# 7_VGA.net
KiCad netlist of a schematic drawn in Altium Designer
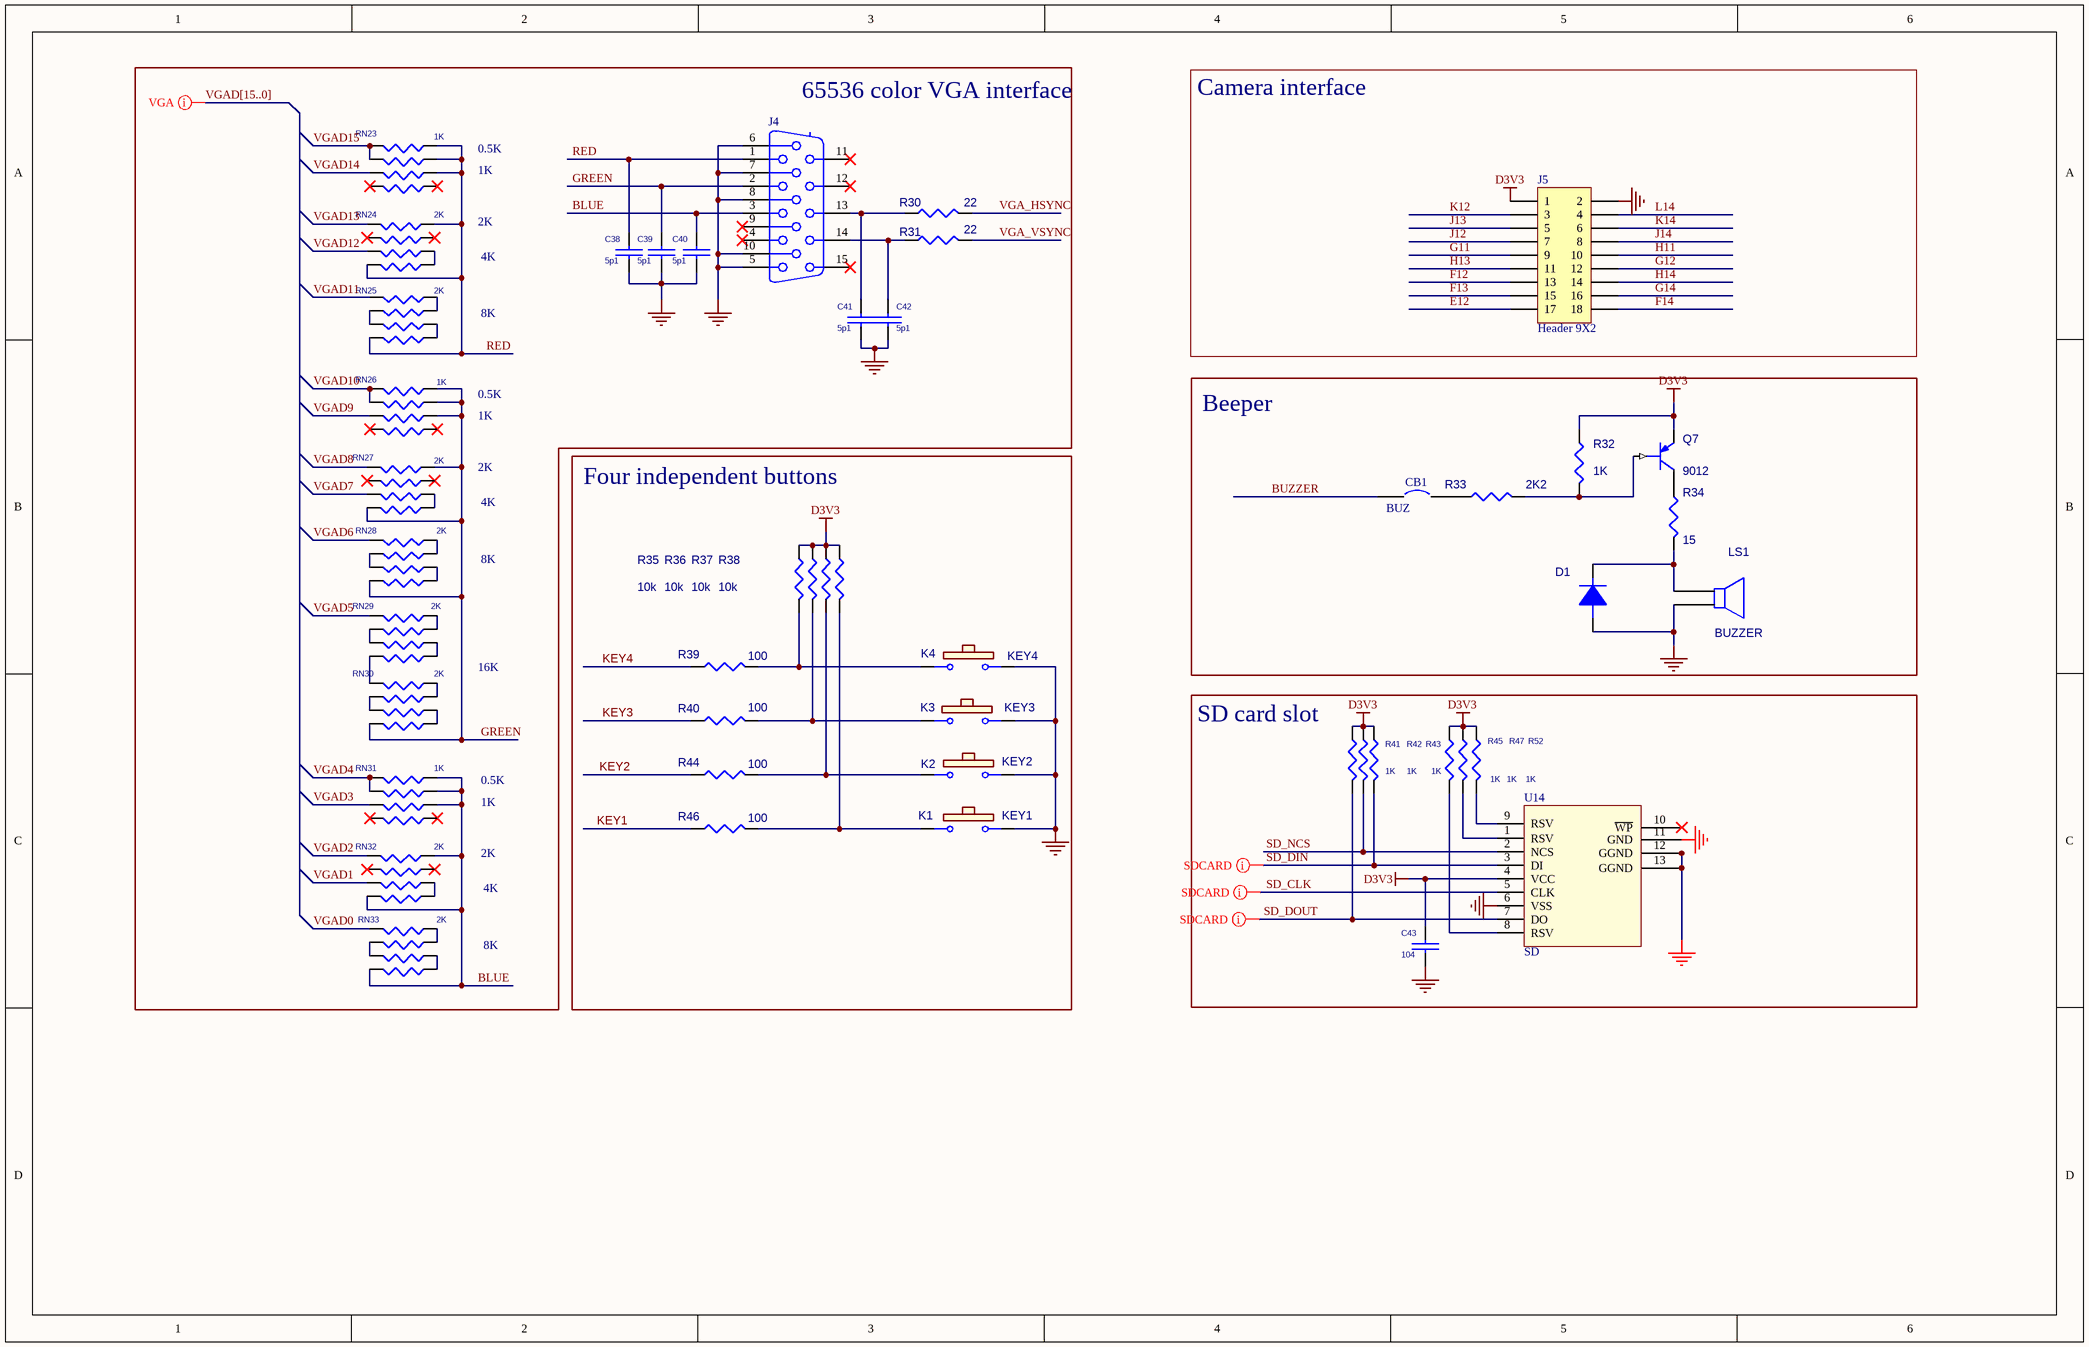
[diagram p0: 7_VGA.SchDoc]

(export (version "E")
  (design (tool "Eeschema 10.0.6"))
  (components
    (comp (ref "C38") (value "5p1") (footprint "0603") (libsource (lib "*") (part "C_Dup1")))
    (comp (ref "C39") (value "5p1") (footprint "0603") (libsource (lib "*") (part "C_Dup1")))
    (comp (ref "C40") (value "5p1") (footprint "0603") (libsource (lib "*") (part "C_Dup1")))
    (comp (ref "C41") (value "5p1") (footprint "0603") (libsource (lib "*") (part "C_Dup1")))
    (comp (ref "C42") (value "5p1") (footprint "0603") (libsource (lib "*") (part "C_Dup1")))
    (comp (ref "C43") (value "104") (footprint "0402") (libsource (lib "*") (part "C_Dup1")))
    (comp (ref "CB1")
      (value "BUZ")
      (footprint "SIP2")
      (description "Circuit Breaker")
      (fields (field (name "PUBLISHER") "Altium Limited"))
      (libsource (lib "Miscellaneous Devices") (part "Circuit Breaker"))
    )
    (comp (ref "D1") (value "~") (footprint "1206") (libsource (lib "Xilinx Spartan-6") (part "4148")))
    (comp (ref "J4")
      (value "~")
      (footprint "VGA")
      (description "Receptacle Assembly, 15-Pin, Sim Line Connector")
      (fields (field (name "PUBLISHER") "Altium Limited"))
      (libsource (lib "Xilinx Spartan-6") (part "Connector 15"))
    )
    (comp (ref "J5")
      (value "Header 9X2")
      (footprint "HDR2X9")
      (description "Header, 9-Pin, Dual row")
      (fields (field (name "PUBLISHER") "Altium Limited"))
      (libsource (lib "Miscellaneous Connectors") (part "Header 9X2"))
    )
    (comp (ref "K1") (value "KEY1") (footprint "KEY735SO") (libsource (lib "*") (part "KEYB")))
    (comp (ref "K2") (value "KEY2") (footprint "KEY735SO") (libsource (lib "*") (part "KEYB")))
    (comp (ref "K3") (value "KEY3") (footprint "KEY735SO") (libsource (lib "") (part "KEYB_1")))
    (comp (ref "K4") (value "KEY4") (footprint "KEY735SO") (libsource (lib "*") (part "KEYB")))
    (comp (ref "LS1") (value "BUZZER") (libsource (lib "*") (part "SPEAKER")))
    (comp (ref "Q7") (value "9012") (footprint "SOT23") (libsource (lib "*") (part "PNP")))
    (comp (ref "R30") (value "22") (footprint "0603") (libsource (lib "*") (part "R")))
    (comp (ref "R31") (value "22") (footprint "0603") (libsource (lib "*") (part "R")))
    (comp (ref "R32") (value "1K") (footprint "0603") (libsource (lib "*") (part "R_Dup3")))
    (comp (ref "R33") (value "2K2") (footprint "0603") (libsource (lib "*") (part "R_Dup3")))
    (comp (ref "R34") (value "15") (footprint "0603") (libsource (lib "*") (part "R_Dup3")))
    (comp (ref "R35") (value "10k") (footprint "0603") (libsource (lib "*") (part "R_Dup2")))
    (comp (ref "R36") (value "10k") (footprint "0603") (libsource (lib "*") (part "R_Dup2")))
    (comp (ref "R37") (value "10k") (footprint "0603") (libsource (lib "*") (part "R_Dup2")))
    (comp (ref "R38") (value "10k") (footprint "0603") (libsource (lib "*") (part "R_Dup2")))
    (comp (ref "R39") (value "100") (footprint "0603") (libsource (lib "*") (part "R_Dup2")))
    (comp (ref "R40") (value "100") (footprint "0603") (libsource (lib "*") (part "R_Dup2")))
    (comp (ref "R41") (value "1K") (footprint "0603") (libsource (lib "*") (part "R")))
    (comp (ref "R42") (value "1K") (footprint "0603") (libsource (lib "*") (part "R")))
    (comp (ref "R43") (value "1K") (footprint "0603") (libsource (lib "*") (part "R")))
    (comp (ref "R44") (value "100") (footprint "0603") (libsource (lib "*") (part "R_Dup2")))
    (comp (ref "R45") (value "1K") (footprint "0603") (libsource (lib "*") (part "R")))
    (comp (ref "R46") (value "100") (footprint "0603") (libsource (lib "*") (part "R_Dup2")))
    (comp (ref "R47") (value "1K") (footprint "0603") (libsource (lib "*") (part "R")))
    (comp (ref "R52") (value "1K") (footprint "0603") (libsource (lib "*") (part "R")))
    (comp (ref "RN23") (value "1K") (footprint "RN-8P") (libsource (lib "*") (part "RN_Dup1")))
    (comp (ref "RN24") (value "2K") (footprint "RN-8P") (libsource (lib "*") (part "RN_Dup1")))
    (comp (ref "RN25") (value "2K") (footprint "RN-8P") (libsource (lib "*") (part "RN_Dup1")))
    (comp (ref "RN26") (value "1K") (footprint "RN-8P") (libsource (lib "*") (part "RN_Dup1")))
    (comp (ref "RN27") (value "2K") (footprint "RN-8P") (libsource (lib "*") (part "RN_Dup1")))
    (comp (ref "RN28") (value "2K") (footprint "RN-8P") (libsource (lib "*") (part "RN_Dup1")))
    (comp (ref "RN29") (value "2K") (footprint "RN-8P") (libsource (lib "*") (part "RN_Dup1")))
    (comp (ref "RN30") (value "2K") (footprint "RN-8P") (libsource (lib "*") (part "RN_Dup1")))
    (comp (ref "RN31") (value "1K") (footprint "RN-8P") (libsource (lib "*") (part "RN_Dup1")))
    (comp (ref "RN32") (value "2K") (footprint "RN-8P") (libsource (lib "*") (part "RN_Dup1")))
    (comp (ref "RN33") (value "2K") (footprint "RN-8P") (libsource (lib "*") (part "RN_Dup1")))
    (comp (ref "U14") (value "SD") (footprint "TF") (libsource (lib "TFT") (part "SD")))
  )
  (nets
    (net (code "1") (name "/BLUE") (class "Default")
      (node (ref "C40") (pin "1") (pinfunction "1_1") (pintype "passive"))
      (node (ref "J4") (pin "3") (pinfunction "3_3") (pintype "passive"))
      (node (ref "RN31") (pin "2") (pinfunction "2_2") (pintype "passive"))
      (node (ref "RN31") (pin "3") (pinfunction "3_3") (pintype "passive"))
      (node (ref "RN31") (pin "4") (pinfunction "4_4") (pintype "passive"))
      (node (ref "RN32") (pin "4") (pinfunction "4_4") (pintype "passive"))
      (node (ref "RN32") (pin "8") (pinfunction "8_8") (pintype "passive"))
      (node (ref "RN33") (pin "8") (pinfunction "8_8") (pintype "passive"))
    )
    (net (code "2") (name "/BUZZER") (class "Default")
      (node (ref "CB1") (pin "1") (pinfunction "1_1") (pintype "passive"))
    )
    (net (code "3") (name "/E12") (class "Default")
      (node (ref "J5") (pin "17") (pinfunction "17_17") (pintype "passive"))
    )
    (net (code "4") (name "/F12") (class "Default")
      (node (ref "J5") (pin "13") (pinfunction "13_13") (pintype "passive"))
    )
    (net (code "5") (name "/F13") (class "Default")
      (node (ref "J5") (pin "15") (pinfunction "15_15") (pintype "passive"))
    )
    (net (code "6") (name "/F14") (class "Default")
      (node (ref "J5") (pin "18") (pinfunction "18_18") (pintype "passive"))
    )
    (net (code "7") (name "/G11") (class "Default")
      (node (ref "J5") (pin "9") (pinfunction "9_9") (pintype "passive"))
    )
    (net (code "8") (name "/G12") (class "Default")
      (node (ref "J5") (pin "12") (pinfunction "12_12") (pintype "passive"))
    )
    (net (code "9") (name "/G14") (class "Default")
      (node (ref "J5") (pin "16") (pinfunction "16_16") (pintype "passive"))
    )
    (net (code "10") (name "/GREEN") (class "Default")
      (node (ref "C39") (pin "1") (pinfunction "1_1") (pintype "passive"))
      (node (ref "J4") (pin "2") (pinfunction "2_2") (pintype "passive"))
      (node (ref "RN26") (pin "2") (pinfunction "2_2") (pintype "passive"))
      (node (ref "RN26") (pin "3") (pinfunction "3_3") (pintype "passive"))
      (node (ref "RN26") (pin "4") (pinfunction "4_4") (pintype "passive"))
      (node (ref "RN27") (pin "4") (pinfunction "4_4") (pintype "passive"))
      (node (ref "RN27") (pin "8") (pinfunction "8_8") (pintype "passive"))
      (node (ref "RN28") (pin "8") (pinfunction "8_8") (pintype "passive"))
      (node (ref "RN30") (pin "8") (pinfunction "8_8") (pintype "passive"))
    )
    (net (code "11") (name "/H11") (class "Default")
      (node (ref "J5") (pin "10") (pinfunction "10_10") (pintype "passive"))
    )
    (net (code "12") (name "/H13") (class "Default")
      (node (ref "J5") (pin "11") (pinfunction "11_11") (pintype "passive"))
    )
    (net (code "13") (name "/H14") (class "Default")
      (node (ref "J5") (pin "14") (pinfunction "14_14") (pintype "passive"))
    )
    (net (code "14") (name "/J12") (class "Default")
      (node (ref "J5") (pin "7") (pinfunction "7_7") (pintype "passive"))
    )
    (net (code "15") (name "/J13") (class "Default")
      (node (ref "J5") (pin "5") (pinfunction "5_5") (pintype "passive"))
    )
    (net (code "16") (name "/J14") (class "Default")
      (node (ref "J5") (pin "8") (pinfunction "8_8") (pintype "passive"))
    )
    (net (code "17") (name "/K12") (class "Default")
      (node (ref "J5") (pin "3") (pinfunction "3_3") (pintype "passive"))
    )
    (net (code "18") (name "/K14") (class "Default")
      (node (ref "J5") (pin "6") (pinfunction "6_6") (pintype "passive"))
    )
    (net (code "19") (name "/KEY1") (class "Default")
      (node (ref "R46") (pin "1") (pinfunction "1_1") (pintype "passive"))
    )
    (net (code "20") (name "/KEY2") (class "Default")
      (node (ref "R44") (pin "1") (pinfunction "1_1") (pintype "passive"))
    )
    (net (code "21") (name "/KEY3") (class "Default")
      (node (ref "R40") (pin "1") (pinfunction "1_1") (pintype "passive"))
    )
    (net (code "22") (name "/KEY4") (class "Default")
      (node (ref "R39") (pin "1") (pinfunction "1_1") (pintype "passive"))
    )
    (net (code "23") (name "/L14") (class "Default")
      (node (ref "J5") (pin "4") (pinfunction "4_4") (pintype "passive"))
    )
    (net (code "24") (name "/RED") (class "Default")
      (node (ref "C38") (pin "1") (pinfunction "1_1") (pintype "passive"))
      (node (ref "J4") (pin "1") (pinfunction "1_1") (pintype "passive"))
      (node (ref "RN23") (pin "2") (pinfunction "2_2") (pintype "passive"))
      (node (ref "RN23") (pin "3") (pinfunction "3_3") (pintype "passive"))
      (node (ref "RN23") (pin "4") (pinfunction "4_4") (pintype "passive"))
      (node (ref "RN24") (pin "4") (pinfunction "4_4") (pintype "passive"))
      (node (ref "RN24") (pin "8") (pinfunction "8_8") (pintype "passive"))
      (node (ref "RN25") (pin "8") (pinfunction "8_8") (pintype "passive"))
    )
    (net (code "25") (name "/SD_CLK") (class "Default")
      (node (ref "U14") (pin "5") (pinfunction "CLK_5") (pintype "passive"))
    )
    (net (code "26") (name "/SD_DIN") (class "Default")
      (node (ref "R43") (pin "2") (pinfunction "2_2") (pintype "passive"))
      (node (ref "U14") (pin "3") (pinfunction "DI_3") (pintype "passive"))
    )
    (net (code "27") (name "/SD_DOUT") (class "Default")
      (node (ref "R41") (pin "2") (pinfunction "2_2") (pintype "passive"))
      (node (ref "U14") (pin "7") (pinfunction "DO_7") (pintype "passive"))
    )
    (net (code "28") (name "/SD_NCS") (class "Default")
      (node (ref "R42") (pin "2") (pinfunction "2_2") (pintype "passive"))
      (node (ref "U14") (pin "2") (pinfunction "NCS_2") (pintype "passive"))
    )
    (net (code "29") (name "/VGAD0") (class "Default")
      (node (ref "RN33") (pin "5") (pinfunction "5_5") (pintype "passive"))
    )
    (net (code "30") (name "/VGAD1") (class "Default")
      (node (ref "RN32") (pin "7") (pinfunction "7_7") (pintype "passive"))
    )
    (net (code "31") (name "/VGAD2") (class "Default")
      (node (ref "RN32") (pin "5") (pinfunction "5_5") (pintype "passive"))
    )
    (net (code "32") (name "/VGAD3") (class "Default")
      (node (ref "RN31") (pin "7") (pinfunction "7_7") (pintype "passive"))
    )
    (net (code "33") (name "/VGAD4") (class "Default")
      (node (ref "RN31") (pin "5") (pinfunction "5_5") (pintype "passive"))
      (node (ref "RN31") (pin "6") (pinfunction "6_6") (pintype "passive"))
    )
    (net (code "34") (name "/VGAD5") (class "Default")
      (node (ref "RN29") (pin "5") (pinfunction "5_5") (pintype "passive"))
    )
    (net (code "35") (name "/VGAD6") (class "Default")
      (node (ref "RN28") (pin "5") (pinfunction "5_5") (pintype "passive"))
    )
    (net (code "36") (name "/VGAD7") (class "Default")
      (node (ref "RN27") (pin "7") (pinfunction "7_7") (pintype "passive"))
    )
    (net (code "37") (name "/VGAD8") (class "Default")
      (node (ref "RN27") (pin "5") (pinfunction "5_5") (pintype "passive"))
    )
    (net (code "38") (name "/VGAD9") (class "Default")
      (node (ref "RN26") (pin "7") (pinfunction "7_7") (pintype "passive"))
    )
    (net (code "39") (name "/VGAD10") (class "Default")
      (node (ref "RN26") (pin "5") (pinfunction "5_5") (pintype "passive"))
      (node (ref "RN26") (pin "6") (pinfunction "6_6") (pintype "passive"))
    )
    (net (code "40") (name "/VGAD11") (class "Default")
      (node (ref "RN25") (pin "5") (pinfunction "5_5") (pintype "passive"))
    )
    (net (code "41") (name "/VGAD12") (class "Default")
      (node (ref "RN24") (pin "7") (pinfunction "7_7") (pintype "passive"))
    )
    (net (code "42") (name "/VGAD13") (class "Default")
      (node (ref "RN24") (pin "5") (pinfunction "5_5") (pintype "passive"))
    )
    (net (code "43") (name "/VGAD14") (class "Default")
      (node (ref "RN23") (pin "7") (pinfunction "7_7") (pintype "passive"))
    )
    (net (code "44") (name "/VGAD15") (class "Default")
      (node (ref "RN23") (pin "5") (pinfunction "5_5") (pintype "passive"))
      (node (ref "RN23") (pin "6") (pinfunction "6_6") (pintype "passive"))
    )
    (net (code "46") (name "/VGA_HSYNC") (class "Default")
      (node (ref "R30") (pin "2") (pinfunction "2_2") (pintype "passive"))
    )
    (net (code "47") (name "/VGA_VSYNC") (class "Default")
      (node (ref "R31") (pin "2") (pinfunction "2_2") (pintype "passive"))
    )
    (net (code "48") (name "D3V3") (class "Default")
      (node (ref "C43") (pin "1") (pinfunction "1_1") (pintype "passive"))
      (node (ref "J5") (pin "1") (pinfunction "1_1") (pintype "passive"))
      (node (ref "Q7") (pin "2") (pinfunction "EMITTER_2") (pintype "passive"))
      (node (ref "R32") (pin "1") (pinfunction "1_1") (pintype "passive"))
      (node (ref "R35") (pin "1") (pinfunction "1_1") (pintype "passive"))
      (node (ref "R36") (pin "1") (pinfunction "1_1") (pintype "passive"))
      (node (ref "R37") (pin "1") (pinfunction "1_1") (pintype "passive"))
      (node (ref "R38") (pin "1") (pinfunction "1_1") (pintype "passive"))
      (node (ref "R41") (pin "1") (pinfunction "1_1") (pintype "passive"))
      (node (ref "R42") (pin "1") (pinfunction "1_1") (pintype "passive"))
      (node (ref "R43") (pin "1") (pinfunction "1_1") (pintype "passive"))
      (node (ref "R45") (pin "1") (pinfunction "1_1") (pintype "passive"))
      (node (ref "R47") (pin "1") (pinfunction "1_1") (pintype "passive"))
      (node (ref "R52") (pin "1") (pinfunction "1_1") (pintype "passive"))
      (node (ref "U14") (pin "4") (pinfunction "VCC_4") (pintype "passive"))
    )
    (net (code "49") (name "GND") (class "Default")
      (node (ref "C38") (pin "2") (pinfunction "2_2") (pintype "passive"))
      (node (ref "C39") (pin "2") (pinfunction "2_2") (pintype "passive"))
      (node (ref "C40") (pin "2") (pinfunction "2_2") (pintype "passive"))
      (node (ref "C41") (pin "2") (pinfunction "2_2") (pintype "passive"))
      (node (ref "C42") (pin "2") (pinfunction "2_2") (pintype "passive"))
      (node (ref "C43") (pin "2") (pinfunction "2_2") (pintype "passive"))
      (node (ref "D1") (pin "1") (pinfunction "A_1") (pintype "passive"))
      (node (ref "J4") (pin "10") (pinfunction "10_10") (pintype "passive"))
      (node (ref "J4") (pin "5") (pinfunction "5_5") (pintype "passive"))
      (node (ref "J4") (pin "6") (pinfunction "6_6") (pintype "passive"))
      (node (ref "J4") (pin "7") (pinfunction "7_7") (pintype "passive"))
      (node (ref "J4") (pin "8") (pinfunction "8_8") (pintype "passive"))
      (node (ref "J5") (pin "2") (pinfunction "2_2") (pintype "passive"))
      (node (ref "K1") (pin "2") (pinfunction "2_2") (pintype "passive"))
      (node (ref "K2") (pin "2") (pinfunction "2_2") (pintype "passive"))
      (node (ref "K3") (pin "1") (pinfunction "1_1") (pintype "passive"))
      (node (ref "K4") (pin "2") (pinfunction "2_2") (pintype "passive"))
      (node (ref "LS1") (pin "2") (pinfunction "2_2") (pintype "passive"))
      (node (ref "U14") (pin "11") (pinfunction "GND_11") (pintype "passive"))
      (node (ref "U14") (pin "12") (pinfunction "GGND_12") (pintype "passive"))
      (node (ref "U14") (pin "13") (pinfunction "GGND_13") (pintype "passive"))
      (node (ref "U14") (pin "6") (pinfunction "VSS_6") (pintype "passive"))
    )
    (net (code "50") (name "Net-(C41-Pad1)") (class "Default")
      (node (ref "C41") (pin "1") (pinfunction "1_1") (pintype "passive"))
      (node (ref "J4") (pin "13") (pinfunction "13_13") (pintype "passive"))
      (node (ref "R30") (pin "1") (pinfunction "1_1") (pintype "passive"))
    )
    (net (code "51") (name "Net-(C42-Pad1)") (class "Default")
      (node (ref "C42") (pin "1") (pinfunction "1_1") (pintype "passive"))
      (node (ref "J4") (pin "14") (pinfunction "14_14") (pintype "passive"))
      (node (ref "R31") (pin "1") (pinfunction "1_1") (pintype "passive"))
    )
    (net (code "52") (name "Net-(CB1-Pad2)") (class "Default")
      (node (ref "CB1") (pin "2") (pinfunction "2_2") (pintype "passive"))
      (node (ref "R33") (pin "1") (pinfunction "1_1") (pintype "passive"))
    )
    (net (code "53") (name "Net-(D1-C)") (class "Default")
      (node (ref "D1") (pin "2") (pinfunction "C_2") (pintype "passive"))
      (node (ref "LS1") (pin "1") (pinfunction "1_1") (pintype "passive"))
      (node (ref "R34") (pin "2") (pinfunction "2_2") (pintype "passive"))
    )
    (net (code "54") (name "Net-(K1-Pad1)") (class "Default")
      (node (ref "K1") (pin "1") (pinfunction "1_1") (pintype "passive"))
      (node (ref "R38") (pin "2") (pinfunction "2_2") (pintype "passive"))
      (node (ref "R46") (pin "2") (pinfunction "2_2") (pintype "passive"))
    )
    (net (code "55") (name "Net-(K2-Pad1)") (class "Default")
      (node (ref "K2") (pin "1") (pinfunction "1_1") (pintype "passive"))
      (node (ref "R37") (pin "2") (pinfunction "2_2") (pintype "passive"))
      (node (ref "R44") (pin "2") (pinfunction "2_2") (pintype "passive"))
    )
    (net (code "56") (name "Net-(K3-Pad2)") (class "Default")
      (node (ref "K3") (pin "2") (pinfunction "2_2") (pintype "passive"))
      (node (ref "R36") (pin "2") (pinfunction "2_2") (pintype "passive"))
      (node (ref "R40") (pin "2") (pinfunction "2_2") (pintype "passive"))
    )
    (net (code "57") (name "Net-(K4-Pad1)") (class "Default")
      (node (ref "K4") (pin "1") (pinfunction "1_1") (pintype "passive"))
      (node (ref "R35") (pin "2") (pinfunction "2_2") (pintype "passive"))
      (node (ref "R39") (pin "2") (pinfunction "2_2") (pintype "passive"))
    )
    (net (code "58") (name "Net-(Q7-BASE)") (class "Default")
      (node (ref "Q7") (pin "1") (pinfunction "BASE_1") (pintype "input"))
      (node (ref "R32") (pin "2") (pinfunction "2_2") (pintype "passive"))
      (node (ref "R33") (pin "2") (pinfunction "2_2") (pintype "passive"))
    )
    (net (code "59") (name "Net-(Q7-COLLECTOR)") (class "Default")
      (node (ref "Q7") (pin "3") (pinfunction "COLLECTOR_3") (pintype "passive"))
      (node (ref "R34") (pin "1") (pinfunction "1_1") (pintype "passive"))
    )
    (net (code "60") (name "Net-(R45-Pad2)") (class "Default")
      (node (ref "R45") (pin "2") (pinfunction "2_2") (pintype "passive"))
      (node (ref "U14") (pin "8") (pinfunction "RSV_8") (pintype "passive"))
    )
    (net (code "61") (name "Net-(R47-Pad2)") (class "Default")
      (node (ref "R47") (pin "2") (pinfunction "2_2") (pintype "passive"))
      (node (ref "U14") (pin "1") (pinfunction "RSV_1") (pintype "passive"))
    )
    (net (code "62") (name "Net-(R52-Pad2)") (class "Default")
      (node (ref "R52") (pin "2") (pinfunction "2_2") (pintype "passive"))
      (node (ref "U14") (pin "9") (pinfunction "RSV_9") (pintype "passive"))
    )
    (net (code "63") (name "Net-(RN24-Pad1)") (class "Default")
      (node (ref "RN24") (pin "1") (pinfunction "1_1") (pintype "passive"))
      (node (ref "RN24") (pin "2") (pinfunction "2_2") (pintype "passive"))
    )
    (net (code "64") (name "Net-(RN25-Pad1)") (class "Default")
      (node (ref "RN25") (pin "1") (pinfunction "1_1") (pintype "passive"))
      (node (ref "RN25") (pin "2") (pinfunction "2_2") (pintype "passive"))
    )
    (net (code "65") (name "Net-(RN25-Pad3)") (class "Default")
      (node (ref "RN25") (pin "3") (pinfunction "3_3") (pintype "passive"))
      (node (ref "RN25") (pin "4") (pinfunction "4_4") (pintype "passive"))
    )
    (net (code "66") (name "Net-(RN25-Pad6)") (class "Default")
      (node (ref "RN25") (pin "6") (pinfunction "6_6") (pintype "passive"))
      (node (ref "RN25") (pin "7") (pinfunction "7_7") (pintype "passive"))
    )
    (net (code "67") (name "Net-(RN27-Pad1)") (class "Default")
      (node (ref "RN27") (pin "1") (pinfunction "1_1") (pintype "passive"))
      (node (ref "RN27") (pin "2") (pinfunction "2_2") (pintype "passive"))
    )
    (net (code "68") (name "Net-(RN28-Pad1)") (class "Default")
      (node (ref "RN28") (pin "1") (pinfunction "1_1") (pintype "passive"))
      (node (ref "RN28") (pin "2") (pinfunction "2_2") (pintype "passive"))
    )
    (net (code "69") (name "Net-(RN28-Pad3)") (class "Default")
      (node (ref "RN28") (pin "3") (pinfunction "3_3") (pintype "passive"))
      (node (ref "RN28") (pin "4") (pinfunction "4_4") (pintype "passive"))
    )
    (net (code "70") (name "Net-(RN28-Pad6)") (class "Default")
      (node (ref "RN28") (pin "6") (pinfunction "6_6") (pintype "passive"))
      (node (ref "RN28") (pin "7") (pinfunction "7_7") (pintype "passive"))
    )
    (net (code "71") (name "Net-(RN29-Pad1)") (class "Default")
      (node (ref "RN29") (pin "1") (pinfunction "1_1") (pintype "passive"))
      (node (ref "RN29") (pin "2") (pinfunction "2_2") (pintype "passive"))
    )
    (net (code "72") (name "Net-(RN29-Pad3)") (class "Default")
      (node (ref "RN29") (pin "3") (pinfunction "3_3") (pintype "passive"))
      (node (ref "RN29") (pin "4") (pinfunction "4_4") (pintype "passive"))
    )
    (net (code "73") (name "Net-(RN29-Pad6)") (class "Default")
      (node (ref "RN29") (pin "6") (pinfunction "6_6") (pintype "passive"))
      (node (ref "RN29") (pin "7") (pinfunction "7_7") (pintype "passive"))
    )
    (net (code "74") (name "Net-(RN29-Pad8)") (class "Default")
      (node (ref "RN29") (pin "8") (pinfunction "8_8") (pintype "passive"))
      (node (ref "RN30") (pin "5") (pinfunction "5_5") (pintype "passive"))
    )
    (net (code "75") (name "Net-(RN30-Pad1)") (class "Default")
      (node (ref "RN30") (pin "1") (pinfunction "1_1") (pintype "passive"))
      (node (ref "RN30") (pin "2") (pinfunction "2_2") (pintype "passive"))
    )
    (net (code "76") (name "Net-(RN30-Pad3)") (class "Default")
      (node (ref "RN30") (pin "3") (pinfunction "3_3") (pintype "passive"))
      (node (ref "RN30") (pin "4") (pinfunction "4_4") (pintype "passive"))
    )
    (net (code "77") (name "Net-(RN30-Pad6)") (class "Default")
      (node (ref "RN30") (pin "6") (pinfunction "6_6") (pintype "passive"))
      (node (ref "RN30") (pin "7") (pinfunction "7_7") (pintype "passive"))
    )
    (net (code "78") (name "Net-(RN32-Pad1)") (class "Default")
      (node (ref "RN32") (pin "1") (pinfunction "1_1") (pintype "passive"))
      (node (ref "RN32") (pin "2") (pinfunction "2_2") (pintype "passive"))
    )
    (net (code "79") (name "Net-(RN33-Pad1)") (class "Default")
      (node (ref "RN33") (pin "1") (pinfunction "1_1") (pintype "passive"))
      (node (ref "RN33") (pin "2") (pinfunction "2_2") (pintype "passive"))
    )
    (net (code "80") (name "Net-(RN33-Pad3)") (class "Default")
      (node (ref "RN33") (pin "3") (pinfunction "3_3") (pintype "passive"))
      (node (ref "RN33") (pin "4") (pinfunction "4_4") (pintype "passive"))
    )
    (net (code "81") (name "Net-(RN33-Pad6)") (class "Default")
      (node (ref "RN33") (pin "6") (pinfunction "6_6") (pintype "passive"))
      (node (ref "RN33") (pin "7") (pinfunction "7_7") (pintype "passive"))
    )
    (net (code "82") (name "unconnected-(J4-MH1-Pad16)") (class "Default")
      (node (ref "J4") (pin "16") (pinfunction "MH1_16") (pintype "passive"))
    )
    (net (code "83") (name "unconnected-(J4-MH2-Pad17)") (class "Default")
      (node (ref "J4") (pin "17") (pinfunction "MH2_17") (pintype "passive"))
    )
    (net (code "84") (name "unconnected-(J4-Pad4)") (class "Default")
      (node (ref "J4") (pin "4") (pinfunction "4_4") (pintype "passive+no_connect"))
    )
    (net (code "85") (name "unconnected-(J4-Pad9)") (class "Default")
      (node (ref "J4") (pin "9") (pinfunction "9_9") (pintype "passive+no_connect"))
    )
    (net (code "86") (name "unconnected-(J4-Pad11)") (class "Default")
      (node (ref "J4") (pin "11") (pinfunction "11_11") (pintype "passive+no_connect"))
    )
    (net (code "87") (name "unconnected-(J4-Pad12)") (class "Default")
      (node (ref "J4") (pin "12") (pinfunction "12_12") (pintype "passive+no_connect"))
    )
    (net (code "88") (name "unconnected-(J4-Pad15)") (class "Default")
      (node (ref "J4") (pin "15") (pinfunction "15_15") (pintype "passive+no_connect"))
    )
    (net (code "89") (name "unconnected-(RN23-Pad1)") (class "Default")
      (node (ref "RN23") (pin "1") (pinfunction "1_1") (pintype "passive+no_connect"))
    )
    (net (code "90") (name "unconnected-(RN23-Pad8)") (class "Default")
      (node (ref "RN23") (pin "8") (pinfunction "8_8") (pintype "passive+no_connect"))
    )
    (net (code "91") (name "unconnected-(RN24-Pad3)") (class "Default")
      (node (ref "RN24") (pin "3") (pinfunction "3_3") (pintype "passive+no_connect"))
    )
    (net (code "92") (name "unconnected-(RN24-Pad6)") (class "Default")
      (node (ref "RN24") (pin "6") (pinfunction "6_6") (pintype "passive+no_connect"))
    )
    (net (code "93") (name "unconnected-(RN26-Pad1)") (class "Default")
      (node (ref "RN26") (pin "1") (pinfunction "1_1") (pintype "passive+no_connect"))
    )
    (net (code "94") (name "unconnected-(RN26-Pad8)") (class "Default")
      (node (ref "RN26") (pin "8") (pinfunction "8_8") (pintype "passive+no_connect"))
    )
    (net (code "95") (name "unconnected-(RN27-Pad3)") (class "Default")
      (node (ref "RN27") (pin "3") (pinfunction "3_3") (pintype "passive+no_connect"))
    )
    (net (code "96") (name "unconnected-(RN27-Pad6)") (class "Default")
      (node (ref "RN27") (pin "6") (pinfunction "6_6") (pintype "passive+no_connect"))
    )
    (net (code "97") (name "unconnected-(RN31-Pad1)") (class "Default")
      (node (ref "RN31") (pin "1") (pinfunction "1_1") (pintype "passive+no_connect"))
    )
    (net (code "98") (name "unconnected-(RN31-Pad8)") (class "Default")
      (node (ref "RN31") (pin "8") (pinfunction "8_8") (pintype "passive+no_connect"))
    )
    (net (code "99") (name "unconnected-(RN32-Pad3)") (class "Default")
      (node (ref "RN32") (pin "3") (pinfunction "3_3") (pintype "passive+no_connect"))
    )
    (net (code "100") (name "unconnected-(RN32-Pad6)") (class "Default")
      (node (ref "RN32") (pin "6") (pinfunction "6_6") (pintype "passive+no_connect"))
    )
    (net (code "101") (name "unconnected-(U14-~{WP}-Pad10)") (class "Default")
      (node (ref "U14") (pin "10") (pinfunction "~{WP}_10") (pintype "passive+no_connect"))
    )
  )
)
